# ProPrj_usb__2025-12-07-23-03-57.net
KiCad netlist of a schematic drawn in EasyEDA Pro
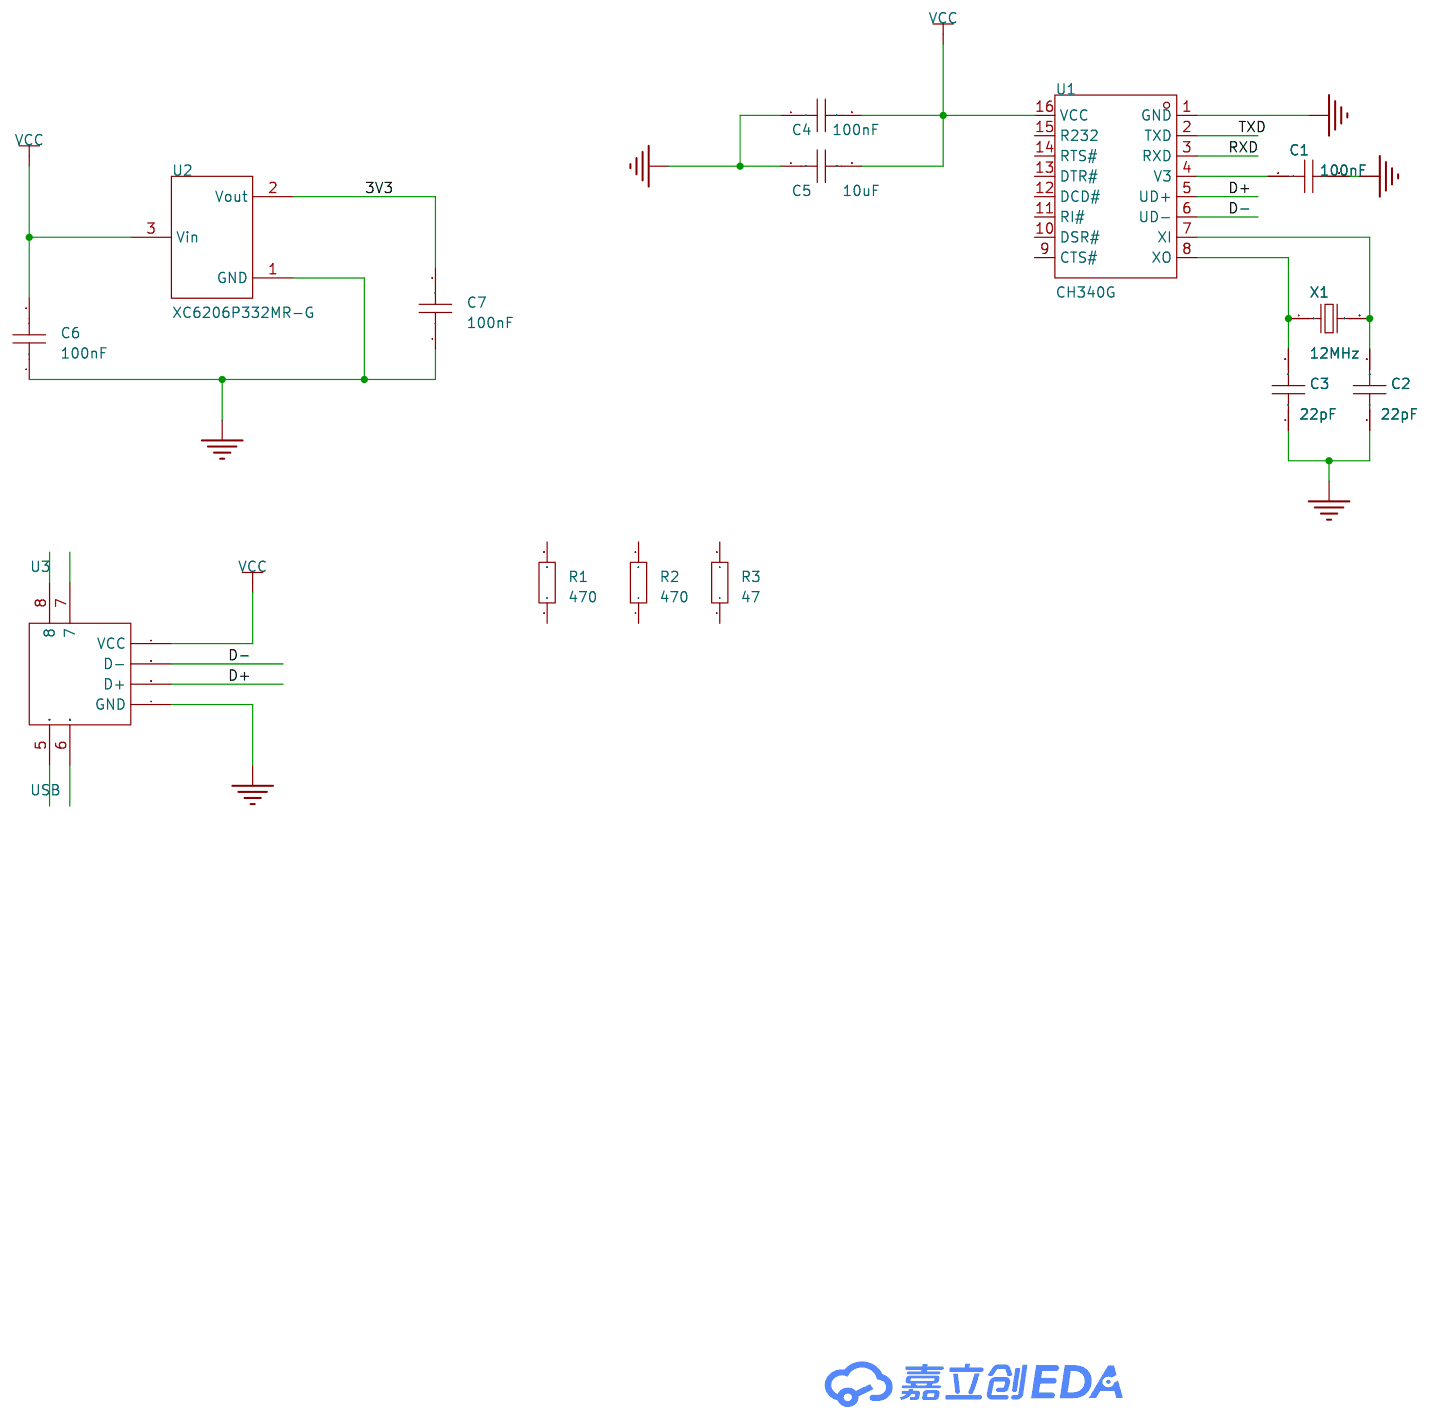
[diagram p0: schematic sheet]

(export (version "E")
  (design (tool "Eeschema 10.0.6"))
  (components
    (comp (ref "C1")
      (value "100nF")
      (footprint "easyedapro:C0603")
      (libsource (lib "easyedapro") (part "Capacitance"))
    )
    (comp (ref "C2")
      (value "22pF")
      (footprint "easyedapro:C0603")
      (libsource (lib "easyedapro") (part "Capacitance"))
    )
    (comp (ref "C3")
      (value "22pF")
      (footprint "easyedapro:C0603")
      (libsource (lib "easyedapro") (part "Capacitance"))
    )
    (comp (ref "C4")
      (value "100nF")
      (footprint "easyedapro:C0603")
      (libsource (lib "easyedapro") (part "Capacitance"))
    )
    (comp (ref "C5")
      (value "10uF")
      (footprint "easyedapro:C0603")
      (libsource (lib "easyedapro") (part "Capacitance"))
    )
    (comp (ref "C6")
      (value "100nF")
      (footprint "easyedapro:C0603")
      (libsource (lib "easyedapro") (part "Capacitance"))
    )
    (comp (ref "C7")
      (value "100nF")
      (footprint "easyedapro:C0603")
      (libsource (lib "easyedapro") (part "Capacitance"))
    )
    (comp (ref "R1") (value "470") (footprint "easyedapro:R0603") (libsource (lib "easyedapro") (part "电阻")))
    (comp (ref "R2") (value "470") (footprint "easyedapro:R0603") (libsource (lib "easyedapro") (part "电阻")))
    (comp (ref "R3") (value "47") (footprint "easyedapro:R0603") (libsource (lib "easyedapro") (part "电阻")))
    (comp (ref "U1")
      (value "CH340G")
      (footprint "easyedapro:SOIC-16_L9.9-W3.9-P1.27-LS6.0-BL")
      (description "应用功能:USB转UART;接口协议:USB 2.0;数据速率:2Mbps;")
      (fields (field (name "Manufacturer") "WCH(南京沁恒)"))
      (libsource (lib "easyedapro") (part "CH340G"))
    )
    (comp (ref "U2")
      (value "XC6206P332MR-G")
      (footprint "easyedapro:SOT-23-3_L2.9-W1.6-P1.90-LS2.8-BR")
      (description "输出类型:固定;工作电压:6V;输出电压:3.3V;输出电流:200mA;电源纹波抑制比(PSRR):-;输出极性:正极;")
      (fields (field (name "Manufacturer") "TOREX(特瑞仕)"))
      (libsource (lib "easyedapro") (part "XC6206P332MR"))
    )
    (comp (ref "U3")
      (value "USB")
      (footprint "easyedapro:USB-SMD_USB_1")
      (libsource (lib "easyedapro") (part "USB"))
    )
    (comp (ref "X1")
      (value "12MHz")
      (footprint "easyedapro:CRYSTAL-SMD_L5.0-W3.2")
      (description "晶振类型:贴片晶振;频率:12MHz;常温频差:±20ppm;负载电容:20pF;频率稳定度:±30ppm;")
      (fields
        (field (name "Manufacturer Part") "XC53G2-12.000-F20LJDT")
        (field (name "Manufacturer") "HCI(杭晶)")
      )
      (libsource (lib "easyedapro") (part "XC53G2-12.000-F20LJDT"))
    )
  )
  (nets
    (net (code "1") (name "/3V3") (class "Default")
      (node (ref "C7") (pin "2") (pinfunction "2_2") (pintype "input"))
      (node (ref "U2") (pin "2") (pinfunction "Vout_2") (pintype "unspecified"))
    )
    (net (code "2") (name "/D+") (class "Default")
      (node (ref "U1") (pin "5") (pinfunction "UD+_5") (pintype "unspecified"))
      (node (ref "U3") (pin "3") (pinfunction "D+_3") (pintype "input"))
    )
    (net (code "3") (name "/D-") (class "Default")
      (node (ref "U1") (pin "6") (pinfunction "UD-_6") (pintype "unspecified"))
      (node (ref "U3") (pin "2") (pinfunction "D-_2") (pintype "input"))
    )
    (net (code "4") (name "/RXD") (class "Default")
      (node (ref "U1") (pin "3") (pinfunction "RXD_3") (pintype "unspecified"))
    )
    (net (code "5") (name "/TXD") (class "Default")
      (node (ref "U1") (pin "2") (pinfunction "TXD_2") (pintype "unspecified"))
    )
    (net (code "6") (name "GND") (class "Default")
      (node (ref "C1") (pin "2") (pinfunction "2_2") (pintype "input"))
      (node (ref "C2") (pin "1") (pinfunction "1_1") (pintype "input"))
      (node (ref "C3") (pin "1") (pinfunction "1_1") (pintype "input"))
      (node (ref "C4") (pin "1") (pinfunction "1_1") (pintype "input"))
      (node (ref "C5") (pin "1") (pinfunction "1_1") (pintype "input"))
      (node (ref "C6") (pin "1") (pinfunction "1_1") (pintype "input"))
      (node (ref "C7") (pin "1") (pinfunction "1_1") (pintype "input"))
      (node (ref "U1") (pin "1") (pinfunction "GND_1") (pintype "unspecified"))
      (node (ref "U2") (pin "1") (pinfunction "GND_1") (pintype "unspecified"))
      (node (ref "U3") (pin "4") (pinfunction "GND_4") (pintype "input"))
    )
    (net (code "7") (name "Net-(U1-V3)") (class "Default")
      (node (ref "C1") (pin "1") (pinfunction "1_1") (pintype "input"))
      (node (ref "U1") (pin "4") (pinfunction "V3_4") (pintype "unspecified"))
    )
    (net (code "8") (name "Net-(U1-XI)") (class "Default")
      (node (ref "C2") (pin "2") (pinfunction "2_2") (pintype "input"))
      (node (ref "U1") (pin "7") (pinfunction "XI_7") (pintype "unspecified"))
      (node (ref "X1") (pin "2") (pinfunction "2_2") (pintype "unspecified"))
    )
    (net (code "9") (name "Net-(U1-XO)") (class "Default")
      (node (ref "C3") (pin "2") (pinfunction "2_2") (pintype "input"))
      (node (ref "U1") (pin "8") (pinfunction "XO_8") (pintype "unspecified"))
      (node (ref "X1") (pin "1") (pinfunction "1_1") (pintype "unspecified"))
    )
    (net (code "10") (name "VCC") (class "Default")
      (node (ref "C4") (pin "2") (pinfunction "2_2") (pintype "input"))
      (node (ref "C5") (pin "2") (pinfunction "2_2") (pintype "input"))
      (node (ref "C6") (pin "2") (pinfunction "2_2") (pintype "input"))
      (node (ref "U1") (pin "16") (pinfunction "VCC_16") (pintype "unspecified"))
      (node (ref "U2") (pin "3") (pinfunction "Vin_3") (pintype "unspecified"))
      (node (ref "U3") (pin "1") (pinfunction "VCC_1") (pintype "input"))
    )
    (net (code "11") (name "unconnected-(R1-Pad1)") (class "Default")
      (node (ref "R1") (pin "1") (pinfunction "1_1") (pintype "input"))
    )
    (net (code "12") (name "unconnected-(R1-Pad2)") (class "Default")
      (node (ref "R1") (pin "2") (pinfunction "2_2") (pintype "input"))
    )
    (net (code "13") (name "unconnected-(R2-Pad1)") (class "Default")
      (node (ref "R2") (pin "1") (pinfunction "1_1") (pintype "input"))
    )
    (net (code "14") (name "unconnected-(R2-Pad2)") (class "Default")
      (node (ref "R2") (pin "2") (pinfunction "2_2") (pintype "input"))
    )
    (net (code "15") (name "unconnected-(R3-Pad1)") (class "Default")
      (node (ref "R3") (pin "1") (pinfunction "1_1") (pintype "input"))
    )
    (net (code "16") (name "unconnected-(R3-Pad2)") (class "Default")
      (node (ref "R3") (pin "2") (pinfunction "2_2") (pintype "input"))
    )
    (net (code "17") (name "unconnected-(U1-CTS#-Pad9)") (class "Default")
      (node (ref "U1") (pin "9") (pinfunction "CTS#_9") (pintype "unspecified"))
    )
    (net (code "18") (name "unconnected-(U1-DCD#-Pad12)") (class "Default")
      (node (ref "U1") (pin "12") (pinfunction "DCD#_12") (pintype "unspecified"))
    )
    (net (code "19") (name "unconnected-(U1-DSR#-Pad10)") (class "Default")
      (node (ref "U1") (pin "10") (pinfunction "DSR#_10") (pintype "unspecified"))
    )
    (net (code "20") (name "unconnected-(U1-DTR#-Pad13)") (class "Default")
      (node (ref "U1") (pin "13") (pinfunction "DTR#_13") (pintype "unspecified"))
    )
    (net (code "21") (name "unconnected-(U1-R232-Pad15)") (class "Default")
      (node (ref "U1") (pin "15") (pinfunction "R232_15") (pintype "unspecified"))
    )
    (net (code "22") (name "unconnected-(U1-RI#-Pad11)") (class "Default")
      (node (ref "U1") (pin "11") (pinfunction "RI#_11") (pintype "unspecified"))
    )
    (net (code "23") (name "unconnected-(U1-RTS#-Pad14)") (class "Default")
      (node (ref "U1") (pin "14") (pinfunction "RTS#_14") (pintype "unspecified"))
    )
    (net (code "24") (name "unconnected-(U3-Pad7)") (class "Default")
      (node (ref "U3") (pin "7") (pinfunction "7_7") (pintype "unspecified"))
    )
    (net (code "25") (name "unconnected-(U3-Pad8)") (class "Default")
      (node (ref "U3") (pin "8") (pinfunction "8_8") (pintype "unspecified"))
    )
    (net (code "26") (name "unconnected-(U3-SH1-Pad5)") (class "Default")
      (node (ref "U3") (pin "5") (pinfunction "SH1_5") (pintype "unspecified"))
    )
    (net (code "27") (name "unconnected-(U3-SH2-Pad6)") (class "Default")
      (node (ref "U3") (pin "6") (pinfunction "SH2_6") (pintype "unspecified"))
    )
  )
)
